# 4-20mA_Inputs__1-3.net
KiCad netlist of a schematic drawn in Altium Designer
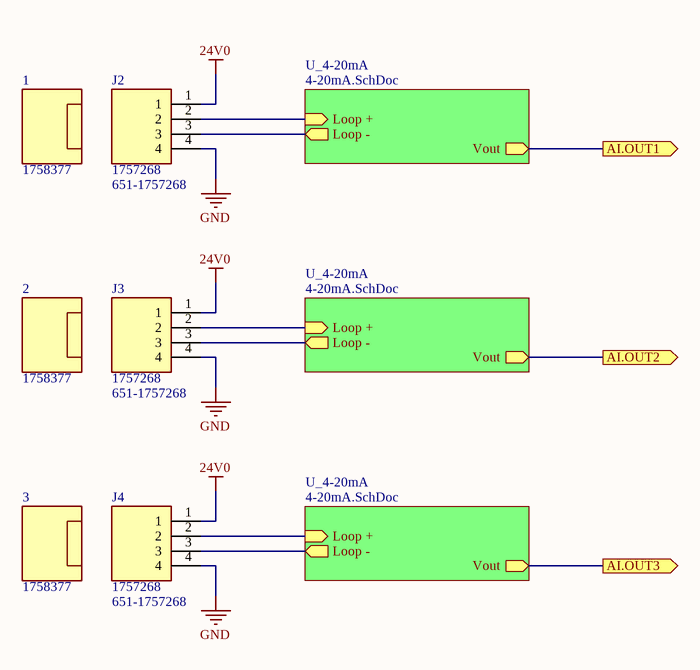
[diagram p0: 4-20mA_Inputs_(1-3).SchDoc]

(export (version "E")
  (design (tool "Eeschema 10.0.6"))
  (components
    (comp (ref "1")
      (value "1758377")
      (footprint "Connector_1758377")
      (description "Plug, Terminal Block; 12 A; 250 V; 5.08 mm; 4 position, screw, Pre-Printed")
      (fields (field (name "MANUFACTURER") "Phoenix Contact") (field (name "VOLTAGE") "300V"))
      (libsource (lib "SamacSys") (part "1758377"))
    )
    (comp (ref "2")
      (value "1758377")
      (footprint "Connector_1758377")
      (description "Plug, Terminal Block; 12 A; 250 V; 5.08 mm; 4 position, screw, Pre-Printed")
      (fields (field (name "MANUFACTURER") "Phoenix Contact") (field (name "VOLTAGE") "300V"))
      (libsource (lib "SamacSys") (part "1758377"))
    )
    (comp (ref "3")
      (value "1758377")
      (footprint "Connector_1758377")
      (description "Plug, Terminal Block; 12 A; 250 V; 5.08 mm; 4 position, screw, Pre-Printed")
      (fields (field (name "MANUFACTURER") "Phoenix Contact") (field (name "VOLTAGE") "300V"))
      (libsource (lib "SamacSys") (part "1758377"))
    )
    (comp (ref "J2")
      (value "1757268")
      (footprint "SHDRRA4W103P0X508_1X4_2232X1200X875P")
      (description "Connector")
      (fields
        (field (name "MOUSER PART NUMBER") "651-1757268")
        (field (name "SUPPLIER PART NUMBER 1") "651-1757268")
      )
      (libsource (lib "SamacSys") (part "1757268"))
    )
    (comp (ref "J3")
      (value "1757268")
      (footprint "SHDRRA4W103P0X508_1X4_2232X1200X875P")
      (description "Connector")
      (fields
        (field (name "MOUSER PART NUMBER") "651-1757268")
        (field (name "SUPPLIER PART NUMBER 1") "651-1757268")
      )
      (libsource (lib "SamacSys") (part "1757268"))
    )
    (comp (ref "J4")
      (value "1757268")
      (footprint "SHDRRA4W103P0X508_1X4_2232X1200X875P")
      (description "Connector")
      (fields
        (field (name "MOUSER PART NUMBER") "651-1757268")
        (field (name "SUPPLIER PART NUMBER 1") "651-1757268")
      )
      (libsource (lib "SamacSys") (part "1757268"))
    )
  )
  (nets
    (net (code "4") (name "/Loop +") (class "Default")
      (node (ref "J2") (pin "2") (pinfunction "2_2") (pintype "passive"))
    )
    (net (code "5") (name "/Loop +_1") (class "Default")
      (node (ref "J4") (pin "2") (pinfunction "2_2") (pintype "passive"))
    )
    (net (code "6") (name "/Loop +_2") (class "Default")
      (node (ref "J3") (pin "2") (pinfunction "2_2") (pintype "passive"))
    )
    (net (code "7") (name "/Loop -") (class "Default")
      (node (ref "J2") (pin "3") (pinfunction "3_3") (pintype "passive"))
    )
    (net (code "8") (name "/Loop -_1") (class "Default")
      (node (ref "J4") (pin "3") (pinfunction "3_3") (pintype "passive"))
    )
    (net (code "9") (name "/Loop -_2") (class "Default")
      (node (ref "J3") (pin "3") (pinfunction "3_3") (pintype "passive"))
    )
    (net (code "10") (name "24V0") (class "Default")
      (node (ref "J2") (pin "1") (pinfunction "1_1") (pintype "passive"))
      (node (ref "J3") (pin "1") (pinfunction "1_1") (pintype "passive"))
      (node (ref "J4") (pin "1") (pinfunction "1_1") (pintype "passive"))
    )
    (net (code "11") (name "GND") (class "Default")
      (node (ref "J2") (pin "4") (pinfunction "4_4") (pintype "passive"))
      (node (ref "J3") (pin "4") (pinfunction "4_4") (pintype "passive"))
      (node (ref "J4") (pin "4") (pinfunction "4_4") (pintype "passive"))
    )
  )
)
